# MicroInterface.net
KiCad netlist of a schematic drawn in Altium Designer
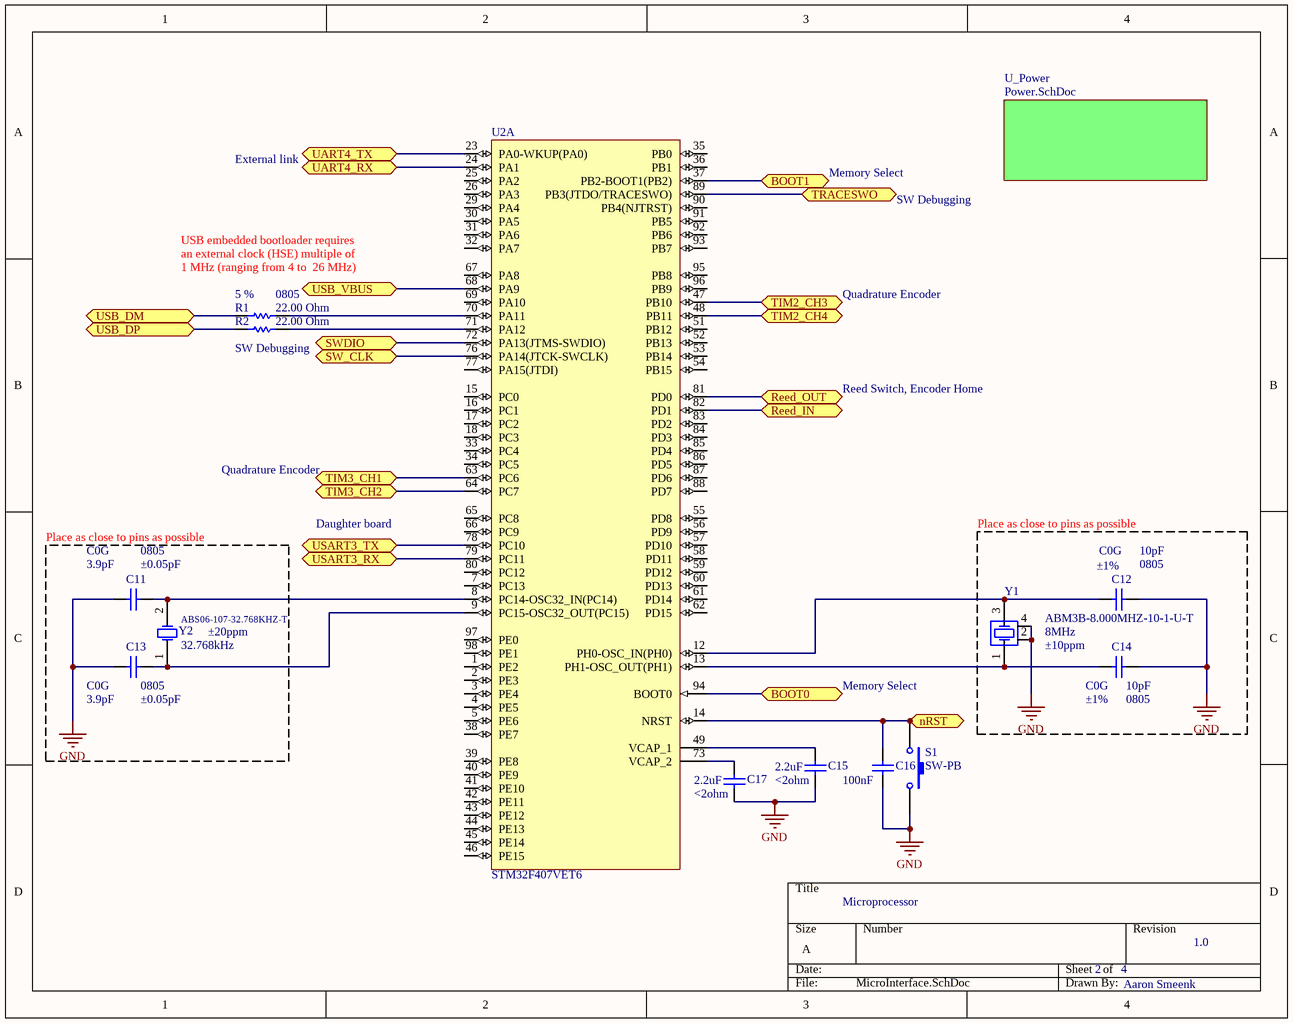
[diagram p0: MicroInterface.SchDoc]

(export (version "E")
  (design (tool "Eeschema 10.0.6"))
  (components
    (comp (ref "C11")
      (value "3.9pF")
      (footprint "CAPC0805(2012)75_L")
      (description "CAP 3.9pF 10V ±0.1pF 0805 (2012 Metric) Thickness 0.75mm SMD")
      (fields
        (field (name "CASE-EIA") "0805")
        (field (name "TOLERANCE") "±0.05pF")
        (field (name "TEMPERATURE COEFFICIENT") "C0G")
        (field (name "MANUFACTURER PART NUMBER") "GRM1555C1H4R0WA01D")
        (field (name "Comment") "CAP 3.9pF 10V 0805(2012)")
      )
      (libsource (lib "Altium Content Vault") (part "CMP-1036-00455-1"))
    )
    (comp (ref "C12")
      (value "10pF")
      (footprint "CAPC0805(2012)100_M")
      (description "CAP 10pF 10V ±0.25pF 0805 (2012 Metric) Thickness 1mm SMD")
      (fields
        (field (name "TOLERANCE") "±1%")
        (field (name "CASE-EIA") "0805")
        (field (name "TEMPERATURE COEFFICIENT") "C0G")
        (field (name "Comment") "CAP 10pF 10V 0805(2012)")
      )
      (libsource (lib "Altium Content Vault") (part "CMP-1036-00821-1"))
    )
    (comp (ref "C13")
      (value "3.9pF")
      (footprint "CAPC0805(2012)75_L")
      (description "CAP 3.9pF 10V ±0.1pF 0805 (2012 Metric) Thickness 0.75mm SMD")
      (fields
        (field (name "CASE-EIA") "0805")
        (field (name "TOLERANCE") "±0.05pF")
        (field (name "TEMPERATURE COEFFICIENT") "C0G")
        (field (name "MANUFACTURER PART NUMBER") "GRM1555C1H4R0WA01D")
        (field (name "Comment") "CAP 3.9pF 10V 0805(2012)")
      )
      (libsource (lib "Altium Content Vault") (part "CMP-1036-00455-1"))
    )
    (comp (ref "C14")
      (value "10pF")
      (footprint "CAPC0805(2012)100_M")
      (description "CAP 10pF 10V ±0.25pF 0805 (2012 Metric) Thickness 1mm SMD")
      (fields
        (field (name "TOLERANCE") "±1%")
        (field (name "CASE-EIA") "0805")
        (field (name "TEMPERATURE COEFFICIENT") "C0G")
        (field (name "Comment") "CAP 10pF 10V 0805(2012)")
      )
      (libsource (lib "Altium Content Vault") (part "CMP-1036-00821-1"))
    )
    (comp (ref "C15")
      (value "2.2uF")
      (footprint "CAPC0805(2012)145_M")
      (description "CAP 1.5uF 6.3V ±20% 0805 (2012 Metric) Thickness 1.45mm SMD")
      (fields
        (field (name "TOLERANCE") "±20%")
        (field (name "ESR") "<2ohm")
        (field (name "Comment") "CAP 1.5uF 6.3V 0805(2012)")
      )
      (libsource (lib "Altium Content Vault") (part "CMP-1036-04784-1"))
    )
    (comp (ref "C16")
      (value "100nF")
      (footprint "CAPC0805(2012)145_M")
      (description "CAP 1.5uF 6.3V ±20% 0805 (2012 Metric) Thickness 1.45mm SMD")
      (fields (field (name "TOLERANCE") "±20%") (field (name "Comment") "CAP 100nF 0805(2012)"))
      (libsource (lib "Altium Content Vault") (part "CMP-1036-04784-1"))
    )
    (comp (ref "C17")
      (value "2.2uF")
      (footprint "CAPC0805(2012)145_M")
      (description "CAP 1.5uF 6.3V ±20% 0805 (2012 Metric) Thickness 1.45mm SMD")
      (fields
        (field (name "TOLERANCE") "±20%")
        (field (name "ESR") "<2ohm")
        (field (name "Comment") "CAP 1.5uF 6.3V 0805(2012)")
      )
      (libsource (lib "Altium Content Vault") (part "CMP-1036-04784-1"))
    )
    (comp (ref "R1")
      (value "22.00 Ohm")
      (footprint "RESC0805(2012)_L")
      (description "22R 0.125W 5% 0805 (2012 Metric)  SMD")
      (fields
        (field (name "POWER") "0.125 W")
        (field (name "TOLERANCE") "5 %")
        (field (name "CASE-EIA") "0805")
        (field (name "Comment") "22R 5% 0805(2012)")
      )
      (libsource (lib "Altium Content Vault") (part "CMP-1013-00034-1"))
    )
    (comp (ref "R2")
      (value "22.00 Ohm")
      (footprint "RESC0805(2012)_L")
      (description "22R 0.125W 5% 0805 (2012 Metric)  SMD")
      (fields (field (name "POWER") "0.125 W") (field (name "TOLERANCE") "5 %"))
      (libsource (lib "Altium Content Vault") (part "CMP-1013-00034-1"))
    )
    (comp (ref "S1")
      (value "SW-PB")
      (footprint "SPST-2")
      (description "Switch")
      (fields (field (name "PUBLISHER") "Altium Limited"))
      (libsource (lib "Miscellaneous Devices") (part "SW-PB"))
    )
    (comp (ref "U2")
      (value "STM32F407VET6")
      (footprint "STM-LQFP100_M")
      (fields (field (name "MANUFACTURER") "STMicroelectronics"))
      (libsource (lib "Altium Content Vault") (part "MC-ARM-STM32F40X_41X-SQ100"))
    )
    (comp (ref "Y1")
      (value "ABM3B-8.000MHZ-10-1-U-T")
      (footprint "ABM3B Series")
      (description "CRYSTAL 8MHZ 10PF SMD")
      (fields (field (name "FREQUENCY") "8MHz") (field (name "FREQUENCY STABILITY") "±10ppm"))
      (libsource (lib "schlib") (part "ABM3B Series"))
    )
    (comp (ref "Y2")
      (value "ABS06-107-32.768KHZ-T")
      (footprint "ABS06-107")
      (description "CRYSTAL 32.768 KHZ 4PF SMD")
      (fields (field (name "FREQUENCY") "32.768kHz") (field (name "FREQUENCY TOLERANCE") "±20ppm"))
      (libsource (lib "schlib") (part "ABS06-107"))
    )
  )
  (nets
    (net (code "1") (name "/BOOT0") (class "Default")
      (node (ref "U2") (pin "94") (pinfunction "BOOT0_94") (pintype "input"))
    )
    (net (code "2") (name "/BOOT1") (class "Default")
      (node (ref "U2") (pin "37") (pinfunction "PB2-BOOT1(PB2)_37") (pintype "bidirectional"))
    )
    (net (code "3") (name "/Reed_IN") (class "Default")
      (node (ref "U2") (pin "82") (pinfunction "PD1_82") (pintype "bidirectional"))
    )
    (net (code "4") (name "/Reed_OUT") (class "Default")
      (node (ref "U2") (pin "81") (pinfunction "PD0_81") (pintype "bidirectional"))
    )
    (net (code "5") (name "/SWDIO") (class "Default")
      (node (ref "U2") (pin "72") (pinfunction "PA13(JTMS-SWDIO)_72") (pintype "bidirectional"))
    )
    (net (code "6") (name "/SW_CLK") (class "Default")
      (node (ref "U2") (pin "76") (pinfunction "PA14(JTCK-SWCLK)_76") (pintype "bidirectional"))
    )
    (net (code "7") (name "/TIM2_CH3") (class "Default")
      (node (ref "U2") (pin "47") (pinfunction "PB10_47") (pintype "bidirectional"))
    )
    (net (code "8") (name "/TIM2_CH4") (class "Default")
      (node (ref "U2") (pin "48") (pinfunction "PB11_48") (pintype "bidirectional"))
    )
    (net (code "9") (name "/TIM3_CH1") (class "Default")
      (node (ref "U2") (pin "63") (pinfunction "PC6_63") (pintype "bidirectional"))
    )
    (net (code "10") (name "/TIM3_CH2") (class "Default")
      (node (ref "U2") (pin "64") (pinfunction "PC7_64") (pintype "bidirectional"))
    )
    (net (code "11") (name "/TRACESWO") (class "Default")
      (node (ref "U2") (pin "89") (pinfunction "PB3(JTDO/TRACESWO)_89") (pintype "bidirectional"))
    )
    (net (code "12") (name "/UART4_RX") (class "Default")
      (node (ref "U2") (pin "24") (pinfunction "PA1_24") (pintype "bidirectional"))
    )
    (net (code "13") (name "/UART4_TX") (class "Default")
      (node (ref "U2") (pin "23") (pinfunction "PA0-WKUP(PA0)_23") (pintype "bidirectional"))
    )
    (net (code "14") (name "/USART3_RX") (class "Default")
      (node (ref "U2") (pin "79") (pinfunction "PC11_79") (pintype "bidirectional"))
    )
    (net (code "15") (name "/USART3_TX") (class "Default")
      (node (ref "U2") (pin "78") (pinfunction "PC10_78") (pintype "bidirectional"))
    )
    (net (code "16") (name "/USB_DM") (class "Default")
      (node (ref "R1") (pin "1") (pinfunction "1_1") (pintype "passive"))
    )
    (net (code "17") (name "/USB_DP") (class "Default")
      (node (ref "R2") (pin "1") (pinfunction "1_1") (pintype "passive"))
    )
    (net (code "18") (name "/USB_VBUS") (class "Default")
      (node (ref "U2") (pin "68") (pinfunction "PA9_68") (pintype "bidirectional"))
    )
    (net (code "19") (name "/nRST") (class "Default")
      (node (ref "C16") (pin "2") (pinfunction "2_2") (pintype "passive"))
      (node (ref "S1") (pin "1") (pinfunction "1_1") (pintype "passive"))
      (node (ref "U2") (pin "14") (pinfunction "NRST_14") (pintype "bidirectional"))
    )
    (net (code "20") (name "GND") (class "Default")
      (node (ref "C11") (pin "1") (pinfunction "1_1") (pintype "passive"))
      (node (ref "C12") (pin "2") (pinfunction "2_2") (pintype "passive"))
      (node (ref "C13") (pin "1") (pinfunction "1_1") (pintype "passive"))
      (node (ref "C14") (pin "2") (pinfunction "2_2") (pintype "passive"))
      (node (ref "C15") (pin "1") (pinfunction "1_1") (pintype "passive"))
      (node (ref "C16") (pin "1") (pinfunction "1_1") (pintype "passive"))
      (node (ref "C17") (pin "1") (pinfunction "1_1") (pintype "passive"))
      (node (ref "S1") (pin "2") (pinfunction "2_2") (pintype "passive"))
      (node (ref "Y1") (pin "2") (pinfunction "2_2") (pintype "passive"))
      (node (ref "Y1") (pin "4") (pinfunction "4_4") (pintype "passive"))
    )
    (net (code "21") (name "Net-(U2A-PA11)") (class "Default")
      (node (ref "R1") (pin "2") (pinfunction "2_2") (pintype "passive"))
      (node (ref "U2") (pin "70") (pinfunction "PA11_70") (pintype "bidirectional"))
    )
    (net (code "22") (name "Net-(U2A-PA12)") (class "Default")
      (node (ref "R2") (pin "2") (pinfunction "2_2") (pintype "passive"))
      (node (ref "U2") (pin "71") (pinfunction "PA12_71") (pintype "bidirectional"))
    )
    (net (code "23") (name "Net-(U2A-PC14-OSC32_IN(PC14))") (class "Default")
      (node (ref "C11") (pin "2") (pinfunction "2_2") (pintype "passive"))
      (node (ref "U2") (pin "8") (pinfunction "PC14-OSC32_IN(PC14)_8") (pintype "bidirectional"))
      (node (ref "Y2") (pin "2") (pinfunction "2_2") (pintype "passive"))
    )
    (net (code "24") (name "Net-(U2A-PC15-OSC32_OUT(PC15))") (class "Default")
      (node (ref "C13") (pin "2") (pinfunction "2_2") (pintype "passive"))
      (node (ref "U2") (pin "9") (pinfunction "PC15-OSC32_OUT(PC15)_9") (pintype "bidirectional"))
      (node (ref "Y2") (pin "1") (pinfunction "1_1") (pintype "passive"))
    )
    (net (code "25") (name "Net-(U2A-PH0-OSC_IN(PH0))") (class "Default")
      (node (ref "C12") (pin "1") (pinfunction "1_1") (pintype "passive"))
      (node (ref "U2") (pin "12") (pinfunction "PH0-OSC_IN(PH0)_12") (pintype "bidirectional"))
      (node (ref "Y1") (pin "3") (pinfunction "3_3") (pintype "passive"))
    )
    (net (code "26") (name "Net-(U2A-PH1-OSC_OUT(PH1))") (class "Default")
      (node (ref "C14") (pin "1") (pinfunction "1_1") (pintype "passive"))
      (node (ref "U2") (pin "13") (pinfunction "PH1-OSC_OUT(PH1)_13") (pintype "bidirectional"))
      (node (ref "Y1") (pin "1") (pinfunction "1_1") (pintype "passive"))
    )
    (net (code "27") (name "Net-(U2A-VCAP_1)") (class "Default")
      (node (ref "C15") (pin "2") (pinfunction "2_2") (pintype "passive"))
      (node (ref "U2") (pin "49") (pinfunction "VCAP_1_49") (pintype "power_in"))
    )
    (net (code "28") (name "Net-(U2A-VCAP_2)") (class "Default")
      (node (ref "C17") (pin "2") (pinfunction "2_2") (pintype "passive"))
      (node (ref "U2") (pin "73") (pinfunction "VCAP_2_73") (pintype "power_in"))
    )
    (net (code "29") (name "unconnected-(U2A-PA2-Pad25)") (class "Default")
      (node (ref "U2") (pin "25") (pinfunction "PA2_25") (pintype "bidirectional"))
    )
    (net (code "30") (name "unconnected-(U2A-PA3-Pad26)") (class "Default")
      (node (ref "U2") (pin "26") (pinfunction "PA3_26") (pintype "bidirectional"))
    )
    (net (code "31") (name "unconnected-(U2A-PA4-Pad29)") (class "Default")
      (node (ref "U2") (pin "29") (pinfunction "PA4_29") (pintype "bidirectional"))
    )
    (net (code "32") (name "unconnected-(U2A-PA5-Pad30)") (class "Default")
      (node (ref "U2") (pin "30") (pinfunction "PA5_30") (pintype "bidirectional"))
    )
    (net (code "33") (name "unconnected-(U2A-PA6-Pad31)") (class "Default")
      (node (ref "U2") (pin "31") (pinfunction "PA6_31") (pintype "bidirectional"))
    )
    (net (code "34") (name "unconnected-(U2A-PA7-Pad32)") (class "Default")
      (node (ref "U2") (pin "32") (pinfunction "PA7_32") (pintype "bidirectional"))
    )
    (net (code "35") (name "unconnected-(U2A-PA8-Pad67)") (class "Default")
      (node (ref "U2") (pin "67") (pinfunction "PA8_67") (pintype "bidirectional"))
    )
    (net (code "36") (name "unconnected-(U2A-PA10-Pad69)") (class "Default")
      (node (ref "U2") (pin "69") (pinfunction "PA10_69") (pintype "bidirectional"))
    )
    (net (code "37") (name "unconnected-(U2A-PA15(JTDI)-Pad77)") (class "Default")
      (node (ref "U2") (pin "77") (pinfunction "PA15(JTDI)_77") (pintype "bidirectional"))
    )
    (net (code "38") (name "unconnected-(U2A-PB0-Pad35)") (class "Default")
      (node (ref "U2") (pin "35") (pinfunction "PB0_35") (pintype "bidirectional"))
    )
    (net (code "39") (name "unconnected-(U2A-PB1-Pad36)") (class "Default")
      (node (ref "U2") (pin "36") (pinfunction "PB1_36") (pintype "bidirectional"))
    )
    (net (code "40") (name "unconnected-(U2A-PB4(NJTRST)-Pad90)") (class "Default")
      (node (ref "U2") (pin "90") (pinfunction "PB4(NJTRST)_90") (pintype "bidirectional"))
    )
    (net (code "41") (name "unconnected-(U2A-PB5-Pad91)") (class "Default")
      (node (ref "U2") (pin "91") (pinfunction "PB5_91") (pintype "bidirectional"))
    )
    (net (code "42") (name "unconnected-(U2A-PB6-Pad92)") (class "Default")
      (node (ref "U2") (pin "92") (pinfunction "PB6_92") (pintype "bidirectional"))
    )
    (net (code "43") (name "unconnected-(U2A-PB7-Pad93)") (class "Default")
      (node (ref "U2") (pin "93") (pinfunction "PB7_93") (pintype "bidirectional"))
    )
    (net (code "44") (name "unconnected-(U2A-PB8-Pad95)") (class "Default")
      (node (ref "U2") (pin "95") (pinfunction "PB8_95") (pintype "bidirectional"))
    )
    (net (code "45") (name "unconnected-(U2A-PB9-Pad96)") (class "Default")
      (node (ref "U2") (pin "96") (pinfunction "PB9_96") (pintype "bidirectional"))
    )
    (net (code "46") (name "unconnected-(U2A-PB12-Pad51)") (class "Default")
      (node (ref "U2") (pin "51") (pinfunction "PB12_51") (pintype "bidirectional"))
    )
    (net (code "47") (name "unconnected-(U2A-PB13-Pad52)") (class "Default")
      (node (ref "U2") (pin "52") (pinfunction "PB13_52") (pintype "bidirectional"))
    )
    (net (code "48") (name "unconnected-(U2A-PB14-Pad53)") (class "Default")
      (node (ref "U2") (pin "53") (pinfunction "PB14_53") (pintype "bidirectional"))
    )
    (net (code "49") (name "unconnected-(U2A-PB15-Pad54)") (class "Default")
      (node (ref "U2") (pin "54") (pinfunction "PB15_54") (pintype "bidirectional"))
    )
    (net (code "50") (name "unconnected-(U2A-PC0-Pad15)") (class "Default")
      (node (ref "U2") (pin "15") (pinfunction "PC0_15") (pintype "bidirectional"))
    )
    (net (code "51") (name "unconnected-(U2A-PC1-Pad16)") (class "Default")
      (node (ref "U2") (pin "16") (pinfunction "PC1_16") (pintype "bidirectional"))
    )
    (net (code "52") (name "unconnected-(U2A-PC2-Pad17)") (class "Default")
      (node (ref "U2") (pin "17") (pinfunction "PC2_17") (pintype "bidirectional"))
    )
    (net (code "53") (name "unconnected-(U2A-PC3-Pad18)") (class "Default")
      (node (ref "U2") (pin "18") (pinfunction "PC3_18") (pintype "bidirectional"))
    )
    (net (code "54") (name "unconnected-(U2A-PC4-Pad33)") (class "Default")
      (node (ref "U2") (pin "33") (pinfunction "PC4_33") (pintype "bidirectional"))
    )
    (net (code "55") (name "unconnected-(U2A-PC5-Pad34)") (class "Default")
      (node (ref "U2") (pin "34") (pinfunction "PC5_34") (pintype "bidirectional"))
    )
    (net (code "56") (name "unconnected-(U2A-PC8-Pad65)") (class "Default")
      (node (ref "U2") (pin "65") (pinfunction "PC8_65") (pintype "bidirectional"))
    )
    (net (code "57") (name "unconnected-(U2A-PC9-Pad66)") (class "Default")
      (node (ref "U2") (pin "66") (pinfunction "PC9_66") (pintype "bidirectional"))
    )
    (net (code "58") (name "unconnected-(U2A-PC12-Pad80)") (class "Default")
      (node (ref "U2") (pin "80") (pinfunction "PC12_80") (pintype "bidirectional"))
    )
    (net (code "59") (name "unconnected-(U2A-PC13-Pad7)") (class "Default")
      (node (ref "U2") (pin "7") (pinfunction "PC13_7") (pintype "bidirectional"))
    )
    (net (code "60") (name "unconnected-(U2A-PD2-Pad83)") (class "Default")
      (node (ref "U2") (pin "83") (pinfunction "PD2_83") (pintype "bidirectional"))
    )
    (net (code "61") (name "unconnected-(U2A-PD3-Pad84)") (class "Default")
      (node (ref "U2") (pin "84") (pinfunction "PD3_84") (pintype "bidirectional"))
    )
    (net (code "62") (name "unconnected-(U2A-PD4-Pad85)") (class "Default")
      (node (ref "U2") (pin "85") (pinfunction "PD4_85") (pintype "bidirectional"))
    )
    (net (code "63") (name "unconnected-(U2A-PD5-Pad86)") (class "Default")
      (node (ref "U2") (pin "86") (pinfunction "PD5_86") (pintype "bidirectional"))
    )
    (net (code "64") (name "unconnected-(U2A-PD6-Pad87)") (class "Default")
      (node (ref "U2") (pin "87") (pinfunction "PD6_87") (pintype "bidirectional"))
    )
    (net (code "65") (name "unconnected-(U2A-PD7-Pad88)") (class "Default")
      (node (ref "U2") (pin "88") (pinfunction "PD7_88") (pintype "bidirectional"))
    )
    (net (code "66") (name "unconnected-(U2A-PD8-Pad55)") (class "Default")
      (node (ref "U2") (pin "55") (pinfunction "PD8_55") (pintype "bidirectional"))
    )
    (net (code "67") (name "unconnected-(U2A-PD9-Pad56)") (class "Default")
      (node (ref "U2") (pin "56") (pinfunction "PD9_56") (pintype "bidirectional"))
    )
    (net (code "68") (name "unconnected-(U2A-PD10-Pad57)") (class "Default")
      (node (ref "U2") (pin "57") (pinfunction "PD10_57") (pintype "bidirectional"))
    )
    (net (code "69") (name "unconnected-(U2A-PD11-Pad58)") (class "Default")
      (node (ref "U2") (pin "58") (pinfunction "PD11_58") (pintype "bidirectional"))
    )
    (net (code "70") (name "unconnected-(U2A-PD12-Pad59)") (class "Default")
      (node (ref "U2") (pin "59") (pinfunction "PD12_59") (pintype "bidirectional"))
    )
    (net (code "71") (name "unconnected-(U2A-PD13-Pad60)") (class "Default")
      (node (ref "U2") (pin "60") (pinfunction "PD13_60") (pintype "bidirectional"))
    )
    (net (code "72") (name "unconnected-(U2A-PD14-Pad61)") (class "Default")
      (node (ref "U2") (pin "61") (pinfunction "PD14_61") (pintype "bidirectional"))
    )
    (net (code "73") (name "unconnected-(U2A-PD15-Pad62)") (class "Default")
      (node (ref "U2") (pin "62") (pinfunction "PD15_62") (pintype "bidirectional"))
    )
    (net (code "74") (name "unconnected-(U2A-PE0-Pad97)") (class "Default")
      (node (ref "U2") (pin "97") (pinfunction "PE0_97") (pintype "bidirectional"))
    )
    (net (code "75") (name "unconnected-(U2A-PE1-Pad98)") (class "Default")
      (node (ref "U2") (pin "98") (pinfunction "PE1_98") (pintype "bidirectional"))
    )
    (net (code "76") (name "unconnected-(U2A-PE2-Pad1)") (class "Default")
      (node (ref "U2") (pin "1") (pinfunction "PE2_1") (pintype "bidirectional"))
    )
    (net (code "77") (name "unconnected-(U2A-PE3-Pad2)") (class "Default")
      (node (ref "U2") (pin "2") (pinfunction "PE3_2") (pintype "bidirectional"))
    )
    (net (code "78") (name "unconnected-(U2A-PE4-Pad3)") (class "Default")
      (node (ref "U2") (pin "3") (pinfunction "PE4_3") (pintype "bidirectional"))
    )
    (net (code "79") (name "unconnected-(U2A-PE5-Pad4)") (class "Default")
      (node (ref "U2") (pin "4") (pinfunction "PE5_4") (pintype "bidirectional"))
    )
    (net (code "80") (name "unconnected-(U2A-PE6-Pad5)") (class "Default")
      (node (ref "U2") (pin "5") (pinfunction "PE6_5") (pintype "bidirectional"))
    )
    (net (code "81") (name "unconnected-(U2A-PE7-Pad38)") (class "Default")
      (node (ref "U2") (pin "38") (pinfunction "PE7_38") (pintype "bidirectional"))
    )
    (net (code "82") (name "unconnected-(U2A-PE8-Pad39)") (class "Default")
      (node (ref "U2") (pin "39") (pinfunction "PE8_39") (pintype "bidirectional"))
    )
    (net (code "83") (name "unconnected-(U2A-PE9-Pad40)") (class "Default")
      (node (ref "U2") (pin "40") (pinfunction "PE9_40") (pintype "bidirectional"))
    )
    (net (code "84") (name "unconnected-(U2A-PE10-Pad41)") (class "Default")
      (node (ref "U2") (pin "41") (pinfunction "PE10_41") (pintype "bidirectional"))
    )
    (net (code "85") (name "unconnected-(U2A-PE11-Pad42)") (class "Default")
      (node (ref "U2") (pin "42") (pinfunction "PE11_42") (pintype "bidirectional"))
    )
    (net (code "86") (name "unconnected-(U2A-PE12-Pad43)") (class "Default")
      (node (ref "U2") (pin "43") (pinfunction "PE12_43") (pintype "bidirectional"))
    )
    (net (code "87") (name "unconnected-(U2A-PE13-Pad44)") (class "Default")
      (node (ref "U2") (pin "44") (pinfunction "PE13_44") (pintype "bidirectional"))
    )
    (net (code "88") (name "unconnected-(U2A-PE14-Pad45)") (class "Default")
      (node (ref "U2") (pin "45") (pinfunction "PE14_45") (pintype "bidirectional"))
    )
    (net (code "89") (name "unconnected-(U2A-PE15-Pad46)") (class "Default")
      (node (ref "U2") (pin "46") (pinfunction "PE15_46") (pintype "bidirectional"))
    )
  )
)
